# VOLTAGE_PEAK.net
KiCad netlist of a schematic drawn in Altium Designer
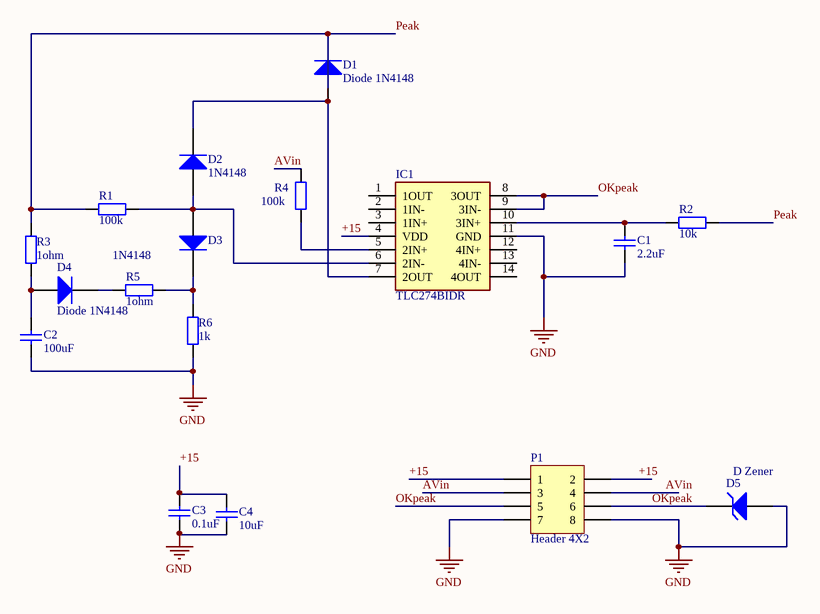
[diagram p0: VOLTAGE_PEAK.SchDoc]

(export (version "E")
  (design (tool "Eeschema 10.0.6"))
  (components
    (comp (ref "C1")
      (value "2.2uF")
      (footprint "C1210")
      (description "Capacitor")
      (fields (field (name "Comment") "Cap") (field (name "PUBLISHER") "Altium Limited"))
      (libsource (lib "Miscellaneous Devices") (part "Cap"))
    )
    (comp (ref "C2")
      (value "100uF")
      (footprint "C1210")
      (description "Capacitor")
      (fields (field (name "Comment") "Cap") (field (name "PUBLISHER") "Altium Limited"))
      (libsource (lib "Miscellaneous Devices") (part "Cap"))
    )
    (comp (ref "C3")
      (value "0.1uF")
      (footprint "1608[0603]")
      (description "Capacitor")
      (fields (field (name "Comment") "Cap") (field (name "PUBLISHER") "Altium Limited"))
      (libsource (lib "Miscellaneous Devices") (part "Cap"))
    )
    (comp (ref "C4")
      (value "10uF")
      (footprint "C1210")
      (description "Capacitor")
      (fields (field (name "Comment") "Cap") (field (name "PUBLISHER") "Altium Limited"))
      (libsource (lib "Miscellaneous Devices") (part "Cap"))
    )
    (comp (ref "D1")
      (value "Diode 1N4148")
      (footprint "DO-35")
      (description "High Conductance Fast Diode")
      (fields (field (name "PUBLISHER") "Altium Limited"))
      (libsource (lib "Miscellaneous Devices") (part "Diode 1N4148"))
    )
    (comp (ref "D2")
      (value "1N4148")
      (footprint "DO-35")
      (description "High Conductance Fast Diode")
      (fields (field (name "PUBLISHER") "Altium Limited"))
      (libsource (lib "Miscellaneous Devices") (part "Diode 1N4148"))
    )
    (comp (ref "D3")
      (value "1N4148")
      (footprint "DO-35")
      (description "High Conductance Fast Diode")
      (fields (field (name "PUBLISHER") "Altium Limited"))
      (libsource (lib "Miscellaneous Devices") (part "Diode 1N4148"))
    )
    (comp (ref "D4")
      (value "Diode 1N4148")
      (footprint "DO-35")
      (description "High Conductance Fast Diode")
      (fields (field (name "PUBLISHER") "Altium Limited"))
      (libsource (lib "Miscellaneous Devices") (part "Diode 1N4148"))
    )
    (comp (ref "D5")
      (value "D Zener")
      (footprint "C1206")
      (description "Zener Diode")
      (fields (field (name "PUBLISHER") "Altium Limited"))
      (libsource (lib "Miscellaneous Devices") (part "D Zener"))
    )
    (comp (ref "IC1")
      (value "TLC274BIDR")
      (footprint "SamacSys:SOIC127P600X175-14N")
      (description "Integrated Circuit")
      (fields (field (name "MOUSER PART NUMBER") "595-TLC274BIDR") (field (name "RS PART NUMBER") "6610212"))
      (libsource (lib "SamacSys") (part "TLC274BIDR"))
    )
    (comp (ref "P1")
      (value "Header 4X2")
      (footprint "HDR2X4")
      (description "Header, 4-Pin, Dual row")
      (fields (field (name "PUBLISHER") "Altium Limited"))
      (libsource (lib "Miscellaneous Connectors") (part "Header 4X2"))
    )
    (comp (ref "R1")
      (value "100k")
      (footprint "C1206")
      (description "Resistor")
      (fields (field (name "Comment") "Res2") (field (name "PUBLISHER") "Altium Limited"))
      (libsource (lib "") (part "Res2_2"))
    )
    (comp (ref "R2")
      (value "10k")
      (footprint "C1206")
      (description "Resistor")
      (fields (field (name "Comment") "Res2") (field (name "PUBLISHER") "Altium Limited"))
      (libsource (lib "") (part "Res2_2"))
    )
    (comp (ref "R3")
      (value "1ohm")
      (footprint "0402")
      (description "Resistor")
      (fields (field (name "Comment") "Res2") (field (name "PUBLISHER") "Altium Limited"))
      (libsource (lib "Miscellaneous Devices") (part "Res2"))
    )
    (comp (ref "R4")
      (value "100k")
      (footprint "C1206")
      (description "Resistor")
      (fields (field (name "Comment") "Res2") (field (name "PUBLISHER") "Altium Limited"))
      (libsource (lib "") (part "Res2_1"))
    )
    (comp (ref "R5")
      (value "1ohm")
      (footprint "0402")
      (description "Resistor")
      (fields (field (name "Comment") "Res2") (field (name "PUBLISHER") "Altium Limited"))
      (libsource (lib "") (part "Res2_2"))
    )
    (comp (ref "R6")
      (value "1k")
      (footprint "C1206")
      (description "Resistor")
      (fields (field (name "Comment") "Res2") (field (name "PUBLISHER") "Altium Limited"))
      (libsource (lib "Miscellaneous Devices") (part "Res2"))
    )
  )
  (nets
    (net (code "1") (name "/+15") (class "Default")
      (node (ref "C3") (pin "2") (pinfunction "2_2") (pintype "passive"))
      (node (ref "C4") (pin "1") (pinfunction "1_1") (pintype "passive"))
      (node (ref "IC1") (pin "4") (pinfunction "VDD_4") (pintype "passive"))
      (node (ref "P1") (pin "1") (pinfunction "1_1") (pintype "passive"))
      (node (ref "P1") (pin "2") (pinfunction "2_2") (pintype "passive"))
    )
    (net (code "2") (name "/AVin") (class "Default")
      (node (ref "P1") (pin "3") (pinfunction "3_3") (pintype "passive"))
      (node (ref "P1") (pin "4") (pinfunction "4_4") (pintype "passive"))
      (node (ref "R4") (pin "1") (pinfunction "1_1") (pintype "passive"))
    )
    (net (code "3") (name "/OKpeak") (class "Default")
      (node (ref "D5") (pin "2") (pinfunction "K_2") (pintype "passive"))
      (node (ref "IC1") (pin "8") (pinfunction "3OUT_8") (pintype "passive"))
      (node (ref "IC1") (pin "9") (pinfunction "3IN-_9") (pintype "passive"))
      (node (ref "P1") (pin "5") (pinfunction "5_5") (pintype "passive"))
      (node (ref "P1") (pin "6") (pinfunction "6_6") (pintype "passive"))
    )
    (net (code "4") (name "/Peak") (class "Default")
      (node (ref "D1") (pin "2") (pinfunction "K_2") (pintype "passive"))
      (node (ref "R1") (pin "1") (pinfunction "1_1") (pintype "passive"))
      (node (ref "R2") (pin "2") (pinfunction "2_2") (pintype "passive"))
      (node (ref "R3") (pin "2") (pinfunction "2_2") (pintype "passive"))
    )
    (net (code "5") (name "GND") (class "Default")
      (node (ref "C1") (pin "2") (pinfunction "2_2") (pintype "passive"))
      (node (ref "C2") (pin "2") (pinfunction "2_2") (pintype "passive"))
      (node (ref "C3") (pin "1") (pinfunction "1_1") (pintype "passive"))
      (node (ref "C4") (pin "2") (pinfunction "2_2") (pintype "passive"))
      (node (ref "D5") (pin "1") (pinfunction "A_1") (pintype "passive"))
      (node (ref "IC1") (pin "11") (pinfunction "GND_11") (pintype "passive"))
      (node (ref "P1") (pin "7") (pinfunction "7_7") (pintype "passive"))
      (node (ref "P1") (pin "8") (pinfunction "8_8") (pintype "passive"))
      (node (ref "R6") (pin "1") (pinfunction "1_1") (pintype "passive"))
    )
    (net (code "6") (name "Net-(D1-A)") (class "Default")
      (node (ref "D1") (pin "1") (pinfunction "A_1") (pintype "passive"))
      (node (ref "D2") (pin "2") (pinfunction "K_2") (pintype "passive"))
      (node (ref "IC1") (pin "7") (pinfunction "2OUT_7") (pintype "passive"))
    )
    (net (code "7") (name "Net-(D2-A)") (class "Default")
      (node (ref "D2") (pin "1") (pinfunction "A_1") (pintype "passive"))
      (node (ref "D3") (pin "1") (pinfunction "A_1") (pintype "passive"))
      (node (ref "IC1") (pin "6") (pinfunction "2IN-_6") (pintype "passive"))
      (node (ref "R1") (pin "2") (pinfunction "2_2") (pintype "passive"))
    )
    (net (code "8") (name "Net-(D3-K)") (class "Default")
      (node (ref "D3") (pin "2") (pinfunction "K_2") (pintype "passive"))
      (node (ref "R5") (pin "2") (pinfunction "2_2") (pintype "passive"))
      (node (ref "R6") (pin "2") (pinfunction "2_2") (pintype "passive"))
    )
    (net (code "9") (name "Net-(D4-A)") (class "Default")
      (node (ref "C2") (pin "1") (pinfunction "1_1") (pintype "passive"))
      (node (ref "D4") (pin "1") (pinfunction "A_1") (pintype "passive"))
      (node (ref "R3") (pin "1") (pinfunction "1_1") (pintype "passive"))
    )
    (net (code "10") (name "Net-(D4-K)") (class "Default")
      (node (ref "D4") (pin "2") (pinfunction "K_2") (pintype "passive"))
      (node (ref "R5") (pin "1") (pinfunction "1_1") (pintype "passive"))
    )
    (net (code "11") (name "Net-(IC1-2IN+)") (class "Default")
      (node (ref "IC1") (pin "5") (pinfunction "2IN+_5") (pintype "passive"))
      (node (ref "R4") (pin "2") (pinfunction "2_2") (pintype "passive"))
    )
    (net (code "12") (name "Net-(IC1-3IN+)") (class "Default")
      (node (ref "C1") (pin "1") (pinfunction "1_1") (pintype "passive"))
      (node (ref "IC1") (pin "10") (pinfunction "3IN+_10") (pintype "passive"))
      (node (ref "R2") (pin "1") (pinfunction "1_1") (pintype "passive"))
    )
    (net (code "13") (name "unconnected-(IC1-1IN+-Pad3)") (class "Default")
      (node (ref "IC1") (pin "3") (pinfunction "1IN+_3") (pintype "passive"))
    )
    (net (code "14") (name "unconnected-(IC1-1IN--Pad2)") (class "Default")
      (node (ref "IC1") (pin "2") (pinfunction "1IN-_2") (pintype "passive"))
    )
    (net (code "15") (name "unconnected-(IC1-1OUT-Pad1)") (class "Default")
      (node (ref "IC1") (pin "1") (pinfunction "1OUT_1") (pintype "passive"))
    )
    (net (code "16") (name "unconnected-(IC1-4IN+-Pad12)") (class "Default")
      (node (ref "IC1") (pin "12") (pinfunction "4IN+_12") (pintype "passive"))
    )
    (net (code "17") (name "unconnected-(IC1-4IN--Pad13)") (class "Default")
      (node (ref "IC1") (pin "13") (pinfunction "4IN-_13") (pintype "passive"))
    )
    (net (code "18") (name "unconnected-(IC1-4OUT-Pad14)") (class "Default")
      (node (ref "IC1") (pin "14") (pinfunction "4OUT_14") (pintype "passive"))
    )
  )
)
